# Sheet1.net
KiCad netlist of a schematic drawn in Altium Designer
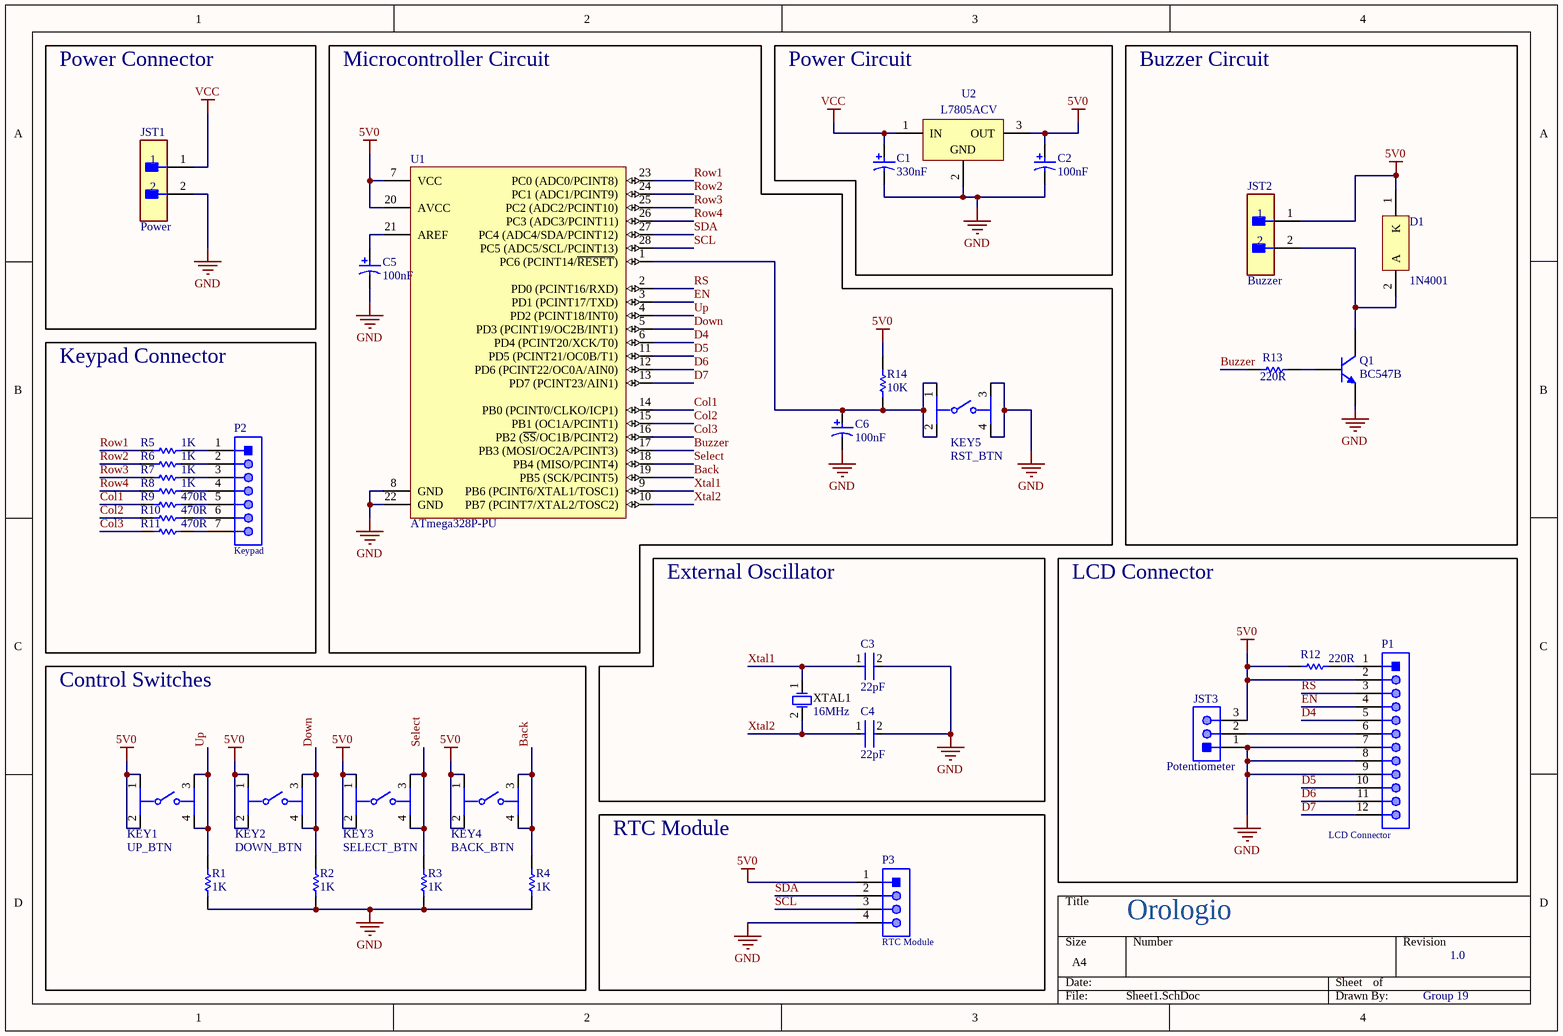
[diagram p0: Sheet1.SchDoc]

(export (version "E")
  (design (tool "Eeschema 10.0.6"))
  (components
    (comp (ref "C1")
      (value "330nF")
      (footprint "CAPPR65-350-1150X800X1250")
      (description "Aluminum Electrolytic Capacitor, 100 uF, +/- 20%, 50 V, -40 to 85 degC, 2-Pin THD, RoHS, Bulk")
      (fields (field (name "MANUFACTURER") "Panasonic") (field (name "VOLTAGE") "50V"))
      (libsource (lib "Altium Content Vault") (part "CAP-P-2"))
    )
    (comp (ref "C2")
      (value "100nF")
      (footprint "CAPPR65-350-1150X800X1250")
      (description "Aluminum Electrolytic Capacitor, 100 uF, +/- 20%, 50 V, -40 to 85 degC, 2-Pin THD, RoHS, Bulk")
      (fields (field (name "MANUFACTURER") "Panasonic") (field (name "VOLTAGE") "50V"))
      (libsource (lib "Altium Content Vault") (part "CAP-P-2"))
    )
    (comp (ref "C3")
      (value "22pF")
      (footprint "FP-RCE0K1-MFG")
      (description "Cap Ceramic 22pF 50V C0G ±5% Radial 5mm +125°C Automotive Bulk")
      (fields (field (name "TOLERANCE") "5%"))
      (libsource (lib "Altium Content Vault") (part "b4654b650e69147ec39a6b967a45e02"))
    )
    (comp (ref "C4")
      (value "22pF")
      (footprint "FP-RCE0K1-MFG")
      (description "Cap Ceramic 22pF 50V C0G ±5% Radial 5mm +125°C Automotive Bulk")
      (fields (field (name "TOLERANCE") "5%"))
      (libsource (lib "Altium Content Vault") (part "b4654b650e69147ec39a6b967a45e02"))
    )
    (comp (ref "C5")
      (value "100nF")
      (footprint "CAPPR65-350-1150X800X1250")
      (description "Aluminum Electrolytic Capacitor, 100 uF, +/- 20%, 50 V, -40 to 85 degC, 2-Pin THD, RoHS, Bulk")
      (fields (field (name "MANUFACTURER") "Panasonic") (field (name "VOLTAGE") "50V"))
      (libsource (lib "Altium Content Vault") (part "CAP-P-2"))
    )
    (comp (ref "C6")
      (value "100nF")
      (footprint "CAPPR65-350-1150X800X1250")
      (description "Aluminum Electrolytic Capacitor, 100 uF, +/- 20%, 50 V, -40 to 85 degC, 2-Pin THD, RoHS, Bulk")
      (fields (field (name "MANUFACTURER") "Panasonic") (field (name "VOLTAGE") "50V"))
      (libsource (lib "Altium Content Vault") (part "CAP-P-2"))
    )
    (comp (ref "D1")
      (value "1N4001")
      (footprint "ONSC-AXIAL_LEAD-2-59-10_P")
      (description "Standard Recovery Rectifier, 2-Pin Axial_Lead, Pb-Free, Bulk Bag")
      (fields (field (name "MANUFACTURER") "On Semiconductor"))
      (libsource (lib "Altium Content Vault") (part "ONSC-D-K1A2-2_A"))
    )
    (comp (ref "JST1")
      (value "Power")
      (footprint "FP-440054-2-MFG")
      (description "CONN HEADER VERT 2POS 2MM")
      (fields
        (field (name "MANUFACTURER") "TE Connectivity")
        (field (name "MANUFACTURER PART NUMBER") "440054-2")
      )
      (libsource (lib "Altium Content Vault") (part "3bc925449376181038e59eaffc5286c"))
    )
    (comp (ref "JST2")
      (value "Buzzer")
      (footprint "FP-440054-2-MFG")
      (description "CONN HEADER VERT 2POS 2MM")
      (fields
        (field (name "MANUFACTURER") "TE Connectivity")
        (field (name "MANUFACTURER PART NUMBER") "440054-2")
      )
      (libsource (lib "Altium Content Vault") (part "3bc925449376181038e59eaffc5286c"))
    )
    (comp (ref "JST3")
      (value "Potentiometer")
      (footprint "JST-B3B-PH-K-S-3_V")
      (fields (field (name "MANUFACTURER") "JST"))
      (libsource (lib "Altium Content Vault") (part "CN-1P-M-R3"))
    )
    (comp (ref "KEY1")
      (value "UP_BTN")
      (footprint "FP-1825910-2-0")
      (description "SWITCH TACTILE SPST-NO 0.05A 24V")
      (fields
        (field (name "OCTOPART") "https://octopart.com/1825910-2-te+connectivity-42270502")
        (field (name "MANUFACTURER") "TE")
      )
      (libsource (lib "Altium Content Vault") (part "b8895f3f4cefb76e1819d2863dba89b"))
    )
    (comp (ref "KEY2")
      (value "DOWN_BTN")
      (footprint "FP-1825910-2-0")
      (description "SWITCH TACTILE SPST-NO 0.05A 24V")
      (fields
        (field (name "OCTOPART") "https://octopart.com/1825910-2-te+connectivity-42270502")
        (field (name "MANUFACTURER") "TE")
      )
      (libsource (lib "Altium Content Vault") (part "b8895f3f4cefb76e1819d2863dba89b"))
    )
    (comp (ref "KEY3")
      (value "SELECT_BTN")
      (footprint "FP-1825910-2-0")
      (description "SWITCH TACTILE SPST-NO 0.05A 24V")
      (fields
        (field (name "OCTOPART") "https://octopart.com/1825910-2-te+connectivity-42270502")
        (field (name "MANUFACTURER") "TE")
      )
      (libsource (lib "Altium Content Vault") (part "b8895f3f4cefb76e1819d2863dba89b"))
    )
    (comp (ref "KEY4")
      (value "BACK_BTN")
      (footprint "FP-1825910-2-0")
      (description "SWITCH TACTILE SPST-NO 0.05A 24V")
      (fields
        (field (name "OCTOPART") "https://octopart.com/1825910-2-te+connectivity-42270502")
        (field (name "MANUFACTURER") "TE")
      )
      (libsource (lib "Altium Content Vault") (part "b8895f3f4cefb76e1819d2863dba89b"))
    )
    (comp (ref "KEY5")
      (value "RST_BTN")
      (footprint "FP-1825910-2-0")
      (description "SWITCH TACTILE SPST-NO 0.05A 24V")
      (fields
        (field (name "OCTOPART") "https://octopart.com/1825910-2-te+connectivity-42270502")
        (field (name "MANUFACTURER") "TE")
      )
      (libsource (lib "Altium Content Vault") (part "b8895f3f4cefb76e1819d2863dba89b"))
    )
    (comp (ref "P1")
      (value "LCD Connector")
      (footprint "61301211121")
      (description "THT Vertical Pin Header WR-PHD, Pitch 2.54 mm, Single Row, 12 pins")
      (fields
        (field (name "PART NUMBER") "61301211121")
        (field (name "MANUFACTURER") "Wurth Elektronik")
        (field (name "PUBLISHER") "WurthElektronik")
      )
      (libsource (lib "Altium Content Vault") (part "WE-CN-1P-M-R12"))
    )
    (comp (ref "P2")
      (value "Keypad")
      (footprint "61300711121")
      (description "THT Vertical Pin Header WR-PHD, Pitch 2.54 mm, Single Row, 7 pins")
      (fields
        (field (name "MANUFACTURER") "Wurth Elektronik")
        (field (name "PART NUMBER") "61300711121")
        (field (name "PUBLISHER") "WurthElektronik")
      )
      (libsource (lib "Altium Content Vault") (part "WE-CN-1P-M-R7"))
    )
    (comp (ref "P3")
      (value "RTC Module")
      (footprint "61300411121")
      (description "THT Vertical Pin Header WR-PHD, Pitch 2.54 mm, Single Row, 4 pins")
      (fields
        (field (name "MANUFACTURER") "Wurth Elektronik")
        (field (name "PART NUMBER") "61300411121")
        (field (name "PUBLISHER") "WurthElektronik")
      )
      (libsource (lib "Altium Content Vault") (part "WE-CN-1P-M-R4"))
    )
    (comp (ref "Q1")
      (value "BC547B")
      (footprint "ONSC-TO-92-3-29-11")
      (description "NPN Bipolar Transistor")
      (fields (field (name "PUBLISHER") "Altium Limited"))
      (libsource (lib "Miscellaneous Devices") (part "NPN"))
    )
    (comp (ref "R1")
      (value "1K")
      (footprint "AXIAL-0.3")
      (description "Resistor")
      (fields (field (name "PUBLISHER") "Altium Limited"))
      (libsource (lib "Miscellaneous Devices") (part "Res1"))
    )
    (comp (ref "R2")
      (value "1K")
      (footprint "AXIAL-0.3")
      (description "Resistor")
      (fields (field (name "PUBLISHER") "Altium Limited"))
      (libsource (lib "Miscellaneous Devices") (part "Res1"))
    )
    (comp (ref "R3")
      (value "1K")
      (footprint "AXIAL-0.3")
      (description "Resistor")
      (fields (field (name "PUBLISHER") "Altium Limited"))
      (libsource (lib "Miscellaneous Devices") (part "Res1"))
    )
    (comp (ref "R4")
      (value "1K")
      (footprint "AXIAL-0.3")
      (description "Resistor")
      (fields (field (name "PUBLISHER") "Altium Limited"))
      (libsource (lib "Miscellaneous Devices") (part "Res1"))
    )
    (comp (ref "R5")
      (value "1K")
      (footprint "AXIAL-0.3")
      (description "Resistor")
      (fields (field (name "PUBLISHER") "Altium Limited"))
      (libsource (lib "Miscellaneous Devices") (part "Res1"))
    )
    (comp (ref "R6")
      (value "1K")
      (footprint "AXIAL-0.3")
      (description "Resistor")
      (fields (field (name "PUBLISHER") "Altium Limited"))
      (libsource (lib "Miscellaneous Devices") (part "Res1"))
    )
    (comp (ref "R7")
      (value "1K")
      (footprint "AXIAL-0.3")
      (description "Resistor")
      (fields (field (name "PUBLISHER") "Altium Limited"))
      (libsource (lib "Miscellaneous Devices") (part "Res1"))
    )
    (comp (ref "R8")
      (value "1K")
      (footprint "AXIAL-0.3")
      (description "Resistor")
      (fields (field (name "PUBLISHER") "Altium Limited"))
      (libsource (lib "Miscellaneous Devices") (part "Res1"))
    )
    (comp (ref "R9")
      (value "470R")
      (footprint "AXIAL-0.3")
      (description "Resistor")
      (fields (field (name "PUBLISHER") "Altium Limited"))
      (libsource (lib "Miscellaneous Devices") (part "Res1"))
    )
    (comp (ref "R10")
      (value "470R")
      (footprint "AXIAL-0.3")
      (description "Resistor")
      (fields (field (name "PUBLISHER") "Altium Limited"))
      (libsource (lib "Miscellaneous Devices") (part "Res1"))
    )
    (comp (ref "R11")
      (value "470R")
      (footprint "AXIAL-0.3")
      (description "Resistor")
      (fields (field (name "PUBLISHER") "Altium Limited"))
      (libsource (lib "Miscellaneous Devices") (part "Res1"))
    )
    (comp (ref "R12")
      (value "220R")
      (footprint "AXIAL-0.3")
      (description "Resistor")
      (fields (field (name "PUBLISHER") "Altium Limited"))
      (libsource (lib "Miscellaneous Devices") (part "Res1"))
    )
    (comp (ref "R13")
      (value "220R")
      (footprint "AXIAL-0.3")
      (description "Resistor")
      (fields (field (name "PUBLISHER") "Altium Limited"))
      (libsource (lib "Miscellaneous Devices") (part "Res1"))
    )
    (comp (ref "R14")
      (value "10K")
      (footprint "AXIAL-0.3")
      (description "Resistor")
      (fields (field (name "PUBLISHER") "Altium Limited"))
      (libsource (lib "Miscellaneous Devices") (part "Res1"))
    )
    (comp (ref "U1")
      (value "ATmega328P-PU")
      (footprint "28P3")
      (libsource (lib "Altium Content Vault") (part "MC-8B-ATM48-IL28"))
    )
    (comp (ref "U2")
      (value "L7805ACV")
      (footprint "TO220")
      (description "Positive Voltage Regulator, 5V, 3-Pin TO-220")
      (libsource (lib "Altium Content Vault") (part "PM-REG-L4940-SIL3"))
    )
    (comp (ref "XTAL1")
      (value "16MHz")
      (footprint "FOX-FOXSLF160-20")
      (description "Resistance Weld Thru-Hole Crystal, 16 MHz, -20 to 70 degC, 2-Pin THD, RoHS, Bulk")
      (fields (field (name "TOLERANCE") "1%"))
      (libsource (lib "Altium Content Vault") (part "XTAL-1-2-2"))
    )
  )
  (nets
    (net (code "1") (name "/Back") (class "Default")
      (node (ref "KEY4") (pin "3") (pinfunction "3_3") (pintype "passive"))
      (node (ref "KEY4") (pin "4") (pinfunction "4_4") (pintype "passive"))
      (node (ref "R4") (pin "2") (pinfunction "2_2") (pintype "passive"))
      (node (ref "U1") (pin "19") (pinfunction "PB5_(SCK/PCINT5)_19") (pintype "bidirectional"))
    )
    (net (code "2") (name "/Buzzer") (class "Default")
      (node (ref "R13") (pin "1") (pinfunction "1_1") (pintype "passive"))
      (node (ref "U1") (pin "17") (pinfunction "PB3_(MOSI/OC2A/PCINT3)_17") (pintype "bidirectional"))
    )
    (net (code "3") (name "/Col1") (class "Default")
      (node (ref "R9") (pin "2") (pinfunction "2_2") (pintype "passive"))
      (node (ref "U1") (pin "14") (pinfunction "PB0_(PCINT0/CLKO/ICP1)_14") (pintype "bidirectional"))
    )
    (net (code "4") (name "/Col2") (class "Default")
      (node (ref "R10") (pin "2") (pinfunction "2_2") (pintype "passive"))
      (node (ref "U1") (pin "15") (pinfunction "PB1_(OC1A/PCINT1)_15") (pintype "bidirectional"))
    )
    (net (code "5") (name "/Col3") (class "Default")
      (node (ref "R11") (pin "2") (pinfunction "2_2") (pintype "passive"))
      (node (ref "U1") (pin "16") (pinfunction "PB2_(~{SS}/OC1B/PCINT2)_16") (pintype "bidirectional"))
    )
    (net (code "6") (name "/D4") (class "Default")
      (node (ref "P1") (pin "5") (pinfunction "5_5") (pintype "passive"))
      (node (ref "U1") (pin "6") (pinfunction "PD4_(PCINT20/XCK/T0)_6") (pintype "bidirectional"))
    )
    (net (code "7") (name "/D5") (class "Default")
      (node (ref "P1") (pin "10") (pinfunction "10_10") (pintype "passive"))
      (node (ref "U1") (pin "11") (pinfunction "PD5_(PCINT21/OC0B/T1)_11") (pintype "bidirectional"))
    )
    (net (code "8") (name "/D6") (class "Default")
      (node (ref "P1") (pin "11") (pinfunction "11_11") (pintype "passive"))
      (node (ref "U1") (pin "12") (pinfunction "PD6_(PCINT22/OC0A/AIN0)_12") (pintype "bidirectional"))
    )
    (net (code "9") (name "/D7") (class "Default")
      (node (ref "P1") (pin "12") (pinfunction "12_12") (pintype "passive"))
      (node (ref "U1") (pin "13") (pinfunction "PD7_(PCINT23/AIN1)_13") (pintype "bidirectional"))
    )
    (net (code "10") (name "/Down") (class "Default")
      (node (ref "KEY2") (pin "3") (pinfunction "3_3") (pintype "passive"))
      (node (ref "KEY2") (pin "4") (pinfunction "4_4") (pintype "passive"))
      (node (ref "R2") (pin "1") (pinfunction "1_1") (pintype "passive"))
      (node (ref "U1") (pin "5") (pinfunction "PD3_(PCINT19/OC2B/INT1)_5") (pintype "bidirectional"))
    )
    (net (code "11") (name "/EN") (class "Default")
      (node (ref "P1") (pin "4") (pinfunction "4_4") (pintype "passive"))
      (node (ref "U1") (pin "3") (pinfunction "PD1_(PCINT17/TXD)_3") (pintype "bidirectional"))
    )
    (net (code "12") (name "/RS") (class "Default")
      (node (ref "P1") (pin "3") (pinfunction "3_3") (pintype "passive"))
      (node (ref "U1") (pin "2") (pinfunction "PD0_(PCINT16/RXD)_2") (pintype "bidirectional"))
    )
    (net (code "13") (name "/Row1") (class "Default")
      (node (ref "R5") (pin "2") (pinfunction "2_2") (pintype "passive"))
      (node (ref "U1") (pin "23") (pinfunction "PC0_(ADC0/PCINT8)_23") (pintype "bidirectional"))
    )
    (net (code "14") (name "/Row2") (class "Default")
      (node (ref "R6") (pin "2") (pinfunction "2_2") (pintype "passive"))
      (node (ref "U1") (pin "24") (pinfunction "PC1_(ADC1/PCINT9)_24") (pintype "bidirectional"))
    )
    (net (code "15") (name "/Row3") (class "Default")
      (node (ref "R7") (pin "2") (pinfunction "2_2") (pintype "passive"))
      (node (ref "U1") (pin "25") (pinfunction "PC2_(ADC2/PCINT10)_25") (pintype "bidirectional"))
    )
    (net (code "16") (name "/Row4") (class "Default")
      (node (ref "R8") (pin "2") (pinfunction "2_2") (pintype "passive"))
      (node (ref "U1") (pin "26") (pinfunction "PC3_(ADC3/PCINT11)_26") (pintype "bidirectional"))
    )
    (net (code "17") (name "/SCL") (class "Default")
      (node (ref "P3") (pin "3") (pinfunction "3_3") (pintype "passive"))
      (node (ref "U1") (pin "28") (pinfunction "PC5_(ADC5/SCL/PCINT13)_28") (pintype "bidirectional"))
    )
    (net (code "18") (name "/SDA") (class "Default")
      (node (ref "P3") (pin "2") (pinfunction "2_2") (pintype "passive"))
      (node (ref "U1") (pin "27") (pinfunction "PC4_(ADC4/SDA/PCINT12)_27") (pintype "bidirectional"))
    )
    (net (code "19") (name "/Select") (class "Default")
      (node (ref "KEY3") (pin "3") (pinfunction "3_3") (pintype "passive"))
      (node (ref "KEY3") (pin "4") (pinfunction "4_4") (pintype "passive"))
      (node (ref "R3") (pin "2") (pinfunction "2_2") (pintype "passive"))
      (node (ref "U1") (pin "18") (pinfunction "PB4_(MISO/PCINT4)_18") (pintype "bidirectional"))
    )
    (net (code "20") (name "/Up") (class "Default")
      (node (ref "KEY1") (pin "3") (pinfunction "3_3") (pintype "passive"))
      (node (ref "KEY1") (pin "4") (pinfunction "4_4") (pintype "passive"))
      (node (ref "R1") (pin "1") (pinfunction "1_1") (pintype "passive"))
      (node (ref "U1") (pin "4") (pinfunction "PD2_(PCINT18/INT0)_4") (pintype "bidirectional"))
    )
    (net (code "21") (name "/Xtal1") (class "Default")
      (node (ref "C3") (pin "1") (pinfunction "1_1") (pintype "passive"))
      (node (ref "U1") (pin "9") (pinfunction "PB6_(PCINT6/XTAL1/TOSC1)_9") (pintype "bidirectional"))
      (node (ref "XTAL1") (pin "1") (pinfunction "1_1") (pintype "passive"))
    )
    (net (code "22") (name "/Xtal2") (class "Default")
      (node (ref "C4") (pin "1") (pinfunction "1_1") (pintype "passive"))
      (node (ref "U1") (pin "10") (pinfunction "PB7_(PCINT7/XTAL2/TOSC2)_10") (pintype "bidirectional"))
      (node (ref "XTAL1") (pin "2") (pinfunction "2_2") (pintype "passive"))
    )
    (net (code "23") (name "5V0") (class "Default")
      (node (ref "C2") (pin "1") (pinfunction "1_1") (pintype "passive"))
      (node (ref "D1") (pin "1") (pinfunction "K_1") (pintype "passive"))
      (node (ref "JST2") (pin "1") (pinfunction "1_1") (pintype "passive"))
      (node (ref "JST3") (pin "3") (pinfunction "3_3") (pintype "passive"))
      (node (ref "KEY1") (pin "1") (pinfunction "1_1") (pintype "passive"))
      (node (ref "KEY1") (pin "2") (pinfunction "2_2") (pintype "passive"))
      (node (ref "KEY2") (pin "1") (pinfunction "1_1") (pintype "passive"))
      (node (ref "KEY2") (pin "2") (pinfunction "2_2") (pintype "passive"))
      (node (ref "KEY3") (pin "1") (pinfunction "1_1") (pintype "passive"))
      (node (ref "KEY3") (pin "2") (pinfunction "2_2") (pintype "passive"))
      (node (ref "KEY4") (pin "1") (pinfunction "1_1") (pintype "passive"))
      (node (ref "KEY4") (pin "2") (pinfunction "2_2") (pintype "passive"))
      (node (ref "P1") (pin "2") (pinfunction "2_2") (pintype "passive"))
      (node (ref "P3") (pin "1") (pinfunction "1_1") (pintype "passive"))
      (node (ref "R12") (pin "1") (pinfunction "1_1") (pintype "passive"))
      (node (ref "R14") (pin "2") (pinfunction "2_2") (pintype "passive"))
      (node (ref "U1") (pin "20") (pinfunction "AVCC_20") (pintype "power_in"))
      (node (ref "U1") (pin "7") (pinfunction "VCC_7") (pintype "power_in"))
      (node (ref "U2") (pin "3") (pinfunction "OUT_3") (pintype "power_in"))
    )
    (net (code "24") (name "GND") (class "Default")
      (node (ref "C1") (pin "2") (pinfunction "2_2") (pintype "passive"))
      (node (ref "C2") (pin "2") (pinfunction "2_2") (pintype "passive"))
      (node (ref "C3") (pin "2") (pinfunction "2_2") (pintype "passive"))
      (node (ref "C4") (pin "2") (pinfunction "2_2") (pintype "passive"))
      (node (ref "C5") (pin "2") (pinfunction "2_2") (pintype "passive"))
      (node (ref "C6") (pin "2") (pinfunction "2_2") (pintype "passive"))
      (node (ref "JST1") (pin "2") (pinfunction "2_2") (pintype "passive"))
      (node (ref "JST3") (pin "1") (pinfunction "1_1") (pintype "passive"))
      (node (ref "KEY5") (pin "3") (pinfunction "3_3") (pintype "passive"))
      (node (ref "KEY5") (pin "4") (pinfunction "4_4") (pintype "passive"))
      (node (ref "P1") (pin "7") (pinfunction "7_7") (pintype "passive"))
      (node (ref "P1") (pin "8") (pinfunction "8_8") (pintype "passive"))
      (node (ref "P1") (pin "9") (pinfunction "9_9") (pintype "passive"))
      (node (ref "P3") (pin "4") (pinfunction "4_4") (pintype "passive"))
      (node (ref "Q1") (pin "3") (pinfunction "E_3") (pintype "passive"))
      (node (ref "R1") (pin "2") (pinfunction "2_2") (pintype "passive"))
      (node (ref "R2") (pin "2") (pinfunction "2_2") (pintype "passive"))
      (node (ref "R3") (pin "1") (pinfunction "1_1") (pintype "passive"))
      (node (ref "R4") (pin "1") (pinfunction "1_1") (pintype "passive"))
      (node (ref "U1") (pin "22") (pinfunction "GND_22") (pintype "power_in"))
      (node (ref "U1") (pin "8") (pinfunction "GND_8") (pintype "power_in"))
      (node (ref "U2") (pin "2") (pinfunction "GND_2") (pintype "power_in"))
    )
    (net (code "25") (name "Net-(D1-A)") (class "Default")
      (node (ref "D1") (pin "2") (pinfunction "A_2") (pintype "passive"))
      (node (ref "JST2") (pin "2") (pinfunction "2_2") (pintype "passive"))
    )
    (net (code "26") (name "Net-(JST3-Pad2)") (class "Default")
      (node (ref "JST3") (pin "2") (pinfunction "2_2") (pintype "passive"))
      (node (ref "P1") (pin "6") (pinfunction "6_6") (pintype "passive"))
    )
    (net (code "27") (name "Net-(P1-Pad1)") (class "Default")
      (node (ref "P1") (pin "1") (pinfunction "1_1") (pintype "passive"))
      (node (ref "R12") (pin "2") (pinfunction "2_2") (pintype "passive"))
    )
    (net (code "28") (name "Net-(P2-Pad1)") (class "Default")
      (node (ref "P2") (pin "1") (pinfunction "1_1") (pintype "passive"))
      (node (ref "R5") (pin "1") (pinfunction "1_1") (pintype "passive"))
    )
    (net (code "29") (name "Net-(P2-Pad2)") (class "Default")
      (node (ref "P2") (pin "2") (pinfunction "2_2") (pintype "passive"))
      (node (ref "R6") (pin "1") (pinfunction "1_1") (pintype "passive"))
    )
    (net (code "30") (name "Net-(P2-Pad3)") (class "Default")
      (node (ref "P2") (pin "3") (pinfunction "3_3") (pintype "passive"))
      (node (ref "R7") (pin "1") (pinfunction "1_1") (pintype "passive"))
    )
    (net (code "31") (name "Net-(P2-Pad4)") (class "Default")
      (node (ref "P2") (pin "4") (pinfunction "4_4") (pintype "passive"))
      (node (ref "R8") (pin "1") (pinfunction "1_1") (pintype "passive"))
    )
    (net (code "32") (name "Net-(P2-Pad5)") (class "Default")
      (node (ref "P2") (pin "5") (pinfunction "5_5") (pintype "passive"))
      (node (ref "R9") (pin "1") (pinfunction "1_1") (pintype "passive"))
    )
    (net (code "33") (name "Net-(P2-Pad6)") (class "Default")
      (node (ref "P2") (pin "6") (pinfunction "6_6") (pintype "passive"))
      (node (ref "R10") (pin "1") (pinfunction "1_1") (pintype "passive"))
    )
    (net (code "34") (name "Net-(P2-Pad7)") (class "Default")
      (node (ref "P2") (pin "7") (pinfunction "7_7") (pintype "passive"))
      (node (ref "R11") (pin "1") (pinfunction "1_1") (pintype "passive"))
    )
    (net (code "35") (name "Net-(Q1-B)") (class "Default")
      (node (ref "Q1") (pin "2") (pinfunction "B_2") (pintype "passive"))
      (node (ref "R13") (pin "2") (pinfunction "2_2") (pintype "passive"))
    )
    (net (code "36") (name "Net-(U1-AREF)") (class "Default")
      (node (ref "C5") (pin "1") (pinfunction "1_1") (pintype "passive"))
      (node (ref "U1") (pin "21") (pinfunction "AREF_21") (pintype "power_in"))
    )
    (net (code "37") (name "Net-(U1-PC6_(PCINT14{slash}~{RESET}))") (class "Default")
      (node (ref "C6") (pin "1") (pinfunction "1_1") (pintype "passive"))
      (node (ref "KEY5") (pin "1") (pinfunction "1_1") (pintype "passive"))
      (node (ref "KEY5") (pin "2") (pinfunction "2_2") (pintype "passive"))
      (node (ref "R14") (pin "1") (pinfunction "1_1") (pintype "passive"))
      (node (ref "U1") (pin "1") (pinfunction "PC6_(PCINT14/~{RESET})_1") (pintype "bidirectional"))
    )
    (net (code "38") (name "VCC") (class "Default")
      (node (ref "C1") (pin "1") (pinfunction "1_1") (pintype "passive"))
      (node (ref "JST1") (pin "1") (pinfunction "1_1") (pintype "passive"))
      (node (ref "U2") (pin "1") (pinfunction "IN_1") (pintype "power_in"))
    )
    (net (code "39") (name "unconnected-(Q1-C-Pad1)") (class "Default")
      (node (ref "Q1") (pin "1") (pinfunction "C_1") (pintype "passive"))
    )
  )
)
